# Sound_Activated_LED_Schematic.net
KiCad netlist of a schematic drawn in EAGLE
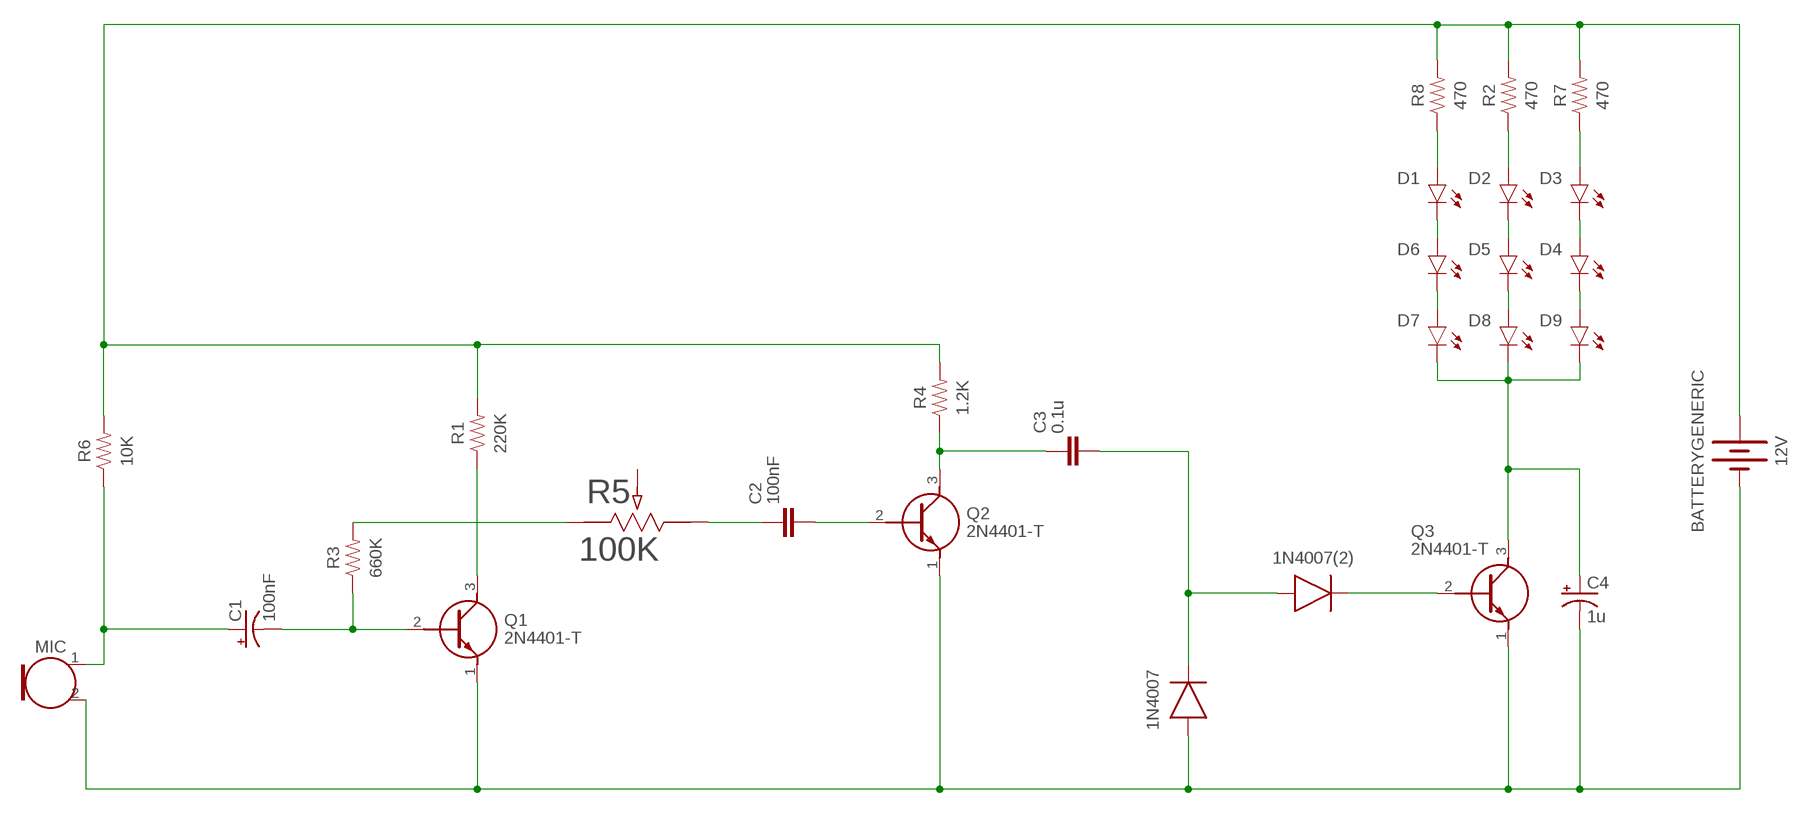
[diagram p0: schematic, sheet 1]

(export (version "E")
  (design (tool "Eeschema 10.0.6"))
  (components
    (comp (ref "1N4007")
      (value "DIODE_1N4148W-7-F_SOD123G")
      (footprint "eagle-import:SOD3715X135")
      (fields (field (name "MANUFACTURER") "Diodes Incorporated") (field (name "MPN") "1N4148W-7-F"))
      (libsource (lib "eagle-import") (part "DIODE__SOD123G1N4148W-7-F"))
    )
    (comp (ref "1N4007(2)")
      (value "DIODE_1N4148W-7-F_SOD123G")
      (footprint "eagle-import:SOD3715X135")
      (fields (field (name "MANUFACTURER") "Diodes Incorporated") (field (name "MPN") "1N4148W-7-F"))
      (libsource (lib "eagle-import") (part "DIODE__SOD123G1N4148W-7-F"))
    )
    (comp (ref "12V")
      (value "BATTERYGENERIC")
      (footprint "eagle-import:BATTERY-GENERIC")
      (libsource (lib "eagle-import") (part "BATTERYGENERIC"))
    )
    (comp (ref "C1")
      (value "100nF")
      (footprint "eagle-import:CAPMP3216X180N")
      (libsource (lib "eagle-import") (part "C-POL-USTANTALUM-1206(3216-METRIC)_"))
    )
    (comp (ref "C2")
      (value "100nF")
      (footprint "eagle-import:CAPC1005X60")
      (libsource (lib "eagle-import") (part "CCHIP-0402(1005-METRIC)_"))
    )
    (comp (ref "C3")
      (value "0.1u")
      (footprint "eagle-import:CAPC1005X60")
      (libsource (lib "eagle-import") (part "CCHIP-0402(1005-METRIC)_"))
    )
    (comp (ref "C4")
      (value "1u")
      (footprint "eagle-import:CAPMP3216X180N")
      (libsource (lib "eagle-import") (part "C-POL-USTANTALUM-1206(3216-METRIC)_"))
    )
    (comp (ref "D1")
      (value "CHIP-ROUND-R_0603")
      (footprint "eagle-import:LEDC1608X65N_RND-R")
      (libsource (lib "eagle-import") (part "CHIP-ROUND-R_0603"))
    )
    (comp (ref "D2")
      (value "CHIP-ROUND-R_0603")
      (footprint "eagle-import:LEDC1608X65N_RND-R")
      (libsource (lib "eagle-import") (part "CHIP-ROUND-R_0603"))
    )
    (comp (ref "D3")
      (value "CHIP-ROUND-R_0603")
      (footprint "eagle-import:LEDC1608X65N_RND-R")
      (libsource (lib "eagle-import") (part "CHIP-ROUND-R_0603"))
    )
    (comp (ref "D4")
      (value "CHIP-ROUND-R_0603")
      (footprint "eagle-import:LEDC1608X65N_RND-R")
      (libsource (lib "eagle-import") (part "CHIP-ROUND-R_0603"))
    )
    (comp (ref "D5")
      (value "CHIP-ROUND-R_0603")
      (footprint "eagle-import:LEDC1608X65N_RND-R")
      (libsource (lib "eagle-import") (part "CHIP-ROUND-R_0603"))
    )
    (comp (ref "D6")
      (value "CHIP-ROUND-R_0603")
      (footprint "eagle-import:LEDC1608X65N_RND-R")
      (libsource (lib "eagle-import") (part "CHIP-ROUND-R_0603"))
    )
    (comp (ref "D7")
      (value "CHIP-ROUND-R_0603")
      (footprint "eagle-import:LEDC1608X65N_RND-R")
      (libsource (lib "eagle-import") (part "CHIP-ROUND-R_0603"))
    )
    (comp (ref "D8")
      (value "CHIP-ROUND-R_0603")
      (footprint "eagle-import:LEDC1608X65N_RND-R")
      (libsource (lib "eagle-import") (part "CHIP-ROUND-R_0603"))
    )
    (comp (ref "D9")
      (value "CHIP-ROUND-R_0603")
      (footprint "eagle-import:LEDC1608X65N_RND-R")
      (libsource (lib "eagle-import") (part "CHIP-ROUND-R_0603"))
    )
    (comp (ref "MIC")
      (value "CMA-4544PF-W")
      (footprint "eagle-import:CMA-4544PF-W")
      (fields (field (name "MANUFACTURER") "Same Sky"))
      (libsource (lib "eagle-import") (part "CMA-4544PF-W"))
    )
    (comp (ref "Q1")
      (value "2N4401-T")
      (footprint "eagle-import:2N4401T")
      (fields (field (name "MOUSER_PART_NUMBER") "583-2N4401-T"))
      (libsource (lib "eagle-import") (part "2N4401-T"))
    )
    (comp (ref "Q2")
      (value "2N4401-T")
      (footprint "eagle-import:2N4401T")
      (fields (field (name "MOUSER_PART_NUMBER") "583-2N4401-T"))
      (libsource (lib "eagle-import") (part "2N4401-T"))
    )
    (comp (ref "Q3")
      (value "2N4401-T")
      (footprint "eagle-import:2N4401T")
      (fields (field (name "MOUSER_PART_NUMBER") "583-2N4401-T"))
      (libsource (lib "eagle-import") (part "2N4401-T"))
    )
    (comp (ref "R1")
      (value "220K")
      (footprint "eagle-import:RESC1005X40")
      (libsource (lib "eagle-import") (part "R-USCHIP-0402(1005-METRIC)_"))
    )
    (comp (ref "R2")
      (value "470")
      (footprint "eagle-import:RESC1005X40")
      (libsource (lib "eagle-import") (part "R-USCHIP-0402(1005-METRIC)_"))
    )
    (comp (ref "R3")
      (value "660K")
      (footprint "eagle-import:RESC1005X40")
      (libsource (lib "eagle-import") (part "R-USCHIP-0402(1005-METRIC)_"))
    )
    (comp (ref "R4")
      (value "1.2K")
      (footprint "eagle-import:RESC1005X40")
      (libsource (lib "eagle-import") (part "R-USCHIP-0402(1005-METRIC)_"))
    )
    (comp (ref "R5")
      (value "100K")
      (footprint "eagle-import:POT_1623757-2")
      (fields
        (field (name "MANUFACTURER_PART_NUMBER") "23ESA103MMF50NF")
        (field (name "COPYRIGHT") "Copyright (C) 2016 Accelerated Designs. All rights reserved")
      )
      (libsource (lib "eagle-import") (part "1623760-2"))
    )
    (comp (ref "R6")
      (value "10K")
      (footprint "eagle-import:RESC1005X40")
      (libsource (lib "eagle-import") (part "R-USCHIP-0402(1005-METRIC)_"))
    )
    (comp (ref "R7")
      (value "470")
      (footprint "eagle-import:RESC1005X40")
      (libsource (lib "eagle-import") (part "R-USCHIP-0402(1005-METRIC)_"))
    )
    (comp (ref "R8")
      (value "470")
      (footprint "eagle-import:RESC1005X40")
      (libsource (lib "eagle-import") (part "R-USCHIP-0402(1005-METRIC)_"))
    )
  )
  (nets
    (net (code "1") (name "Net-(1N4007(2)-A)") (class "Default")
      (node (ref "1N4007") (pin "1") (pinfunction "C_1") (pintype "passive"))
      (node (ref "1N4007(2)") (pin "2") (pinfunction "A_2") (pintype "passive"))
      (node (ref "C3") (pin "2") (pinfunction "2_2") (pintype "passive"))
    )
    (net (code "2") (name "Net-(1N4007(2)-C)") (class "Default")
      (node (ref "1N4007(2)") (pin "1") (pinfunction "C_1") (pintype "passive"))
      (node (ref "Q3") (pin "2") (pinfunction "B_2") (pintype "bidirectional"))
    )
    (net (code "3") (name "Net-(1N4007-A)") (class "Default")
      (node (ref "12V") (pin "-") (pinfunction "-_-") (pintype "passive"))
      (node (ref "1N4007") (pin "2") (pinfunction "A_2") (pintype "passive"))
      (node (ref "C4") (pin "2") (pinfunction "-_2") (pintype "passive"))
      (node (ref "MIC") (pin "2") (pinfunction "GND_2") (pintype "output"))
      (node (ref "Q1") (pin "1") (pinfunction "E_1") (pintype "bidirectional"))
      (node (ref "Q2") (pin "1") (pinfunction "E_1") (pintype "bidirectional"))
      (node (ref "Q3") (pin "1") (pinfunction "E_1") (pintype "bidirectional"))
    )
    (net (code "4") (name "Net-(12V-Pad+)") (class "Default")
      (node (ref "12V") (pin "+") (pinfunction "+_+") (pintype "passive"))
      (node (ref "R1") (pin "2") (pinfunction "2_2") (pintype "passive"))
      (node (ref "R2") (pin "2") (pinfunction "2_2") (pintype "passive"))
      (node (ref "R4") (pin "2") (pinfunction "2_2") (pintype "passive"))
      (node (ref "R6") (pin "2") (pinfunction "2_2") (pintype "passive"))
      (node (ref "R7") (pin "2") (pinfunction "2_2") (pintype "passive"))
      (node (ref "R8") (pin "2") (pinfunction "2_2") (pintype "passive"))
    )
    (net (code "5") (name "Net-(C1-+)") (class "Default")
      (node (ref "C1") (pin "1") (pinfunction "+_1") (pintype "passive"))
      (node (ref "MIC") (pin "1") (pinfunction "OUT_1") (pintype "power_in"))
      (node (ref "R6") (pin "1") (pinfunction "1_1") (pintype "passive"))
    )
    (net (code "6") (name "Net-(C1--)") (class "Default")
      (node (ref "C1") (pin "2") (pinfunction "-_2") (pintype "passive"))
      (node (ref "Q1") (pin "2") (pinfunction "B_2") (pintype "bidirectional"))
      (node (ref "R3") (pin "1") (pinfunction "1_1") (pintype "passive"))
    )
    (net (code "7") (name "Net-(C2-Pad1)") (class "Default")
      (node (ref "C2") (pin "1") (pinfunction "1_1") (pintype "passive"))
      (node (ref "R5") (pin "3") (pinfunction "3_3") (pintype "passive"))
    )
    (net (code "8") (name "Net-(C4-+)") (class "Default")
      (node (ref "C4") (pin "1") (pinfunction "+_1") (pintype "passive"))
      (node (ref "D7") (pin "C") (pinfunction "C_C") (pintype "passive"))
      (node (ref "D8") (pin "C") (pinfunction "C_C") (pintype "passive"))
      (node (ref "D9") (pin "C") (pinfunction "C_C") (pintype "passive"))
      (node (ref "Q3") (pin "3") (pinfunction "C_3") (pintype "bidirectional"))
    )
    (net (code "9") (name "Net-(D1-PadA)") (class "Default")
      (node (ref "D1") (pin "A") (pinfunction "A_A") (pintype "passive"))
      (node (ref "R8") (pin "1") (pinfunction "1_1") (pintype "passive"))
    )
    (net (code "10") (name "Net-(D1-PadC)") (class "Default")
      (node (ref "D1") (pin "C") (pinfunction "C_C") (pintype "passive"))
      (node (ref "D6") (pin "A") (pinfunction "A_A") (pintype "passive"))
    )
    (net (code "11") (name "Net-(D2-PadA)") (class "Default")
      (node (ref "D2") (pin "A") (pinfunction "A_A") (pintype "passive"))
      (node (ref "R2") (pin "1") (pinfunction "1_1") (pintype "passive"))
    )
    (net (code "12") (name "Net-(D2-PadC)") (class "Default")
      (node (ref "D2") (pin "C") (pinfunction "C_C") (pintype "passive"))
      (node (ref "D5") (pin "A") (pinfunction "A_A") (pintype "passive"))
    )
    (net (code "13") (name "Net-(D3-PadA)") (class "Default")
      (node (ref "D3") (pin "A") (pinfunction "A_A") (pintype "passive"))
      (node (ref "R7") (pin "1") (pinfunction "1_1") (pintype "passive"))
    )
    (net (code "14") (name "Net-(D3-PadC)") (class "Default")
      (node (ref "D3") (pin "C") (pinfunction "C_C") (pintype "passive"))
      (node (ref "D4") (pin "A") (pinfunction "A_A") (pintype "passive"))
    )
    (net (code "15") (name "Net-(D4-PadC)") (class "Default")
      (node (ref "D4") (pin "C") (pinfunction "C_C") (pintype "passive"))
      (node (ref "D9") (pin "A") (pinfunction "A_A") (pintype "passive"))
    )
    (net (code "16") (name "Net-(D5-PadC)") (class "Default")
      (node (ref "D5") (pin "C") (pinfunction "C_C") (pintype "passive"))
      (node (ref "D8") (pin "A") (pinfunction "A_A") (pintype "passive"))
    )
    (net (code "17") (name "Net-(D6-PadC)") (class "Default")
      (node (ref "D6") (pin "C") (pinfunction "C_C") (pintype "passive"))
      (node (ref "D7") (pin "A") (pinfunction "A_A") (pintype "passive"))
    )
    (net (code "18") (name "Net-(Q1-C)") (class "Default")
      (node (ref "Q1") (pin "3") (pinfunction "C_3") (pintype "bidirectional"))
      (node (ref "R1") (pin "1") (pinfunction "1_1") (pintype "passive"))
    )
    (net (code "19") (name "Net-(Q2-B)") (class "Default")
      (node (ref "C2") (pin "2") (pinfunction "2_2") (pintype "passive"))
      (node (ref "Q2") (pin "2") (pinfunction "B_2") (pintype "bidirectional"))
    )
    (net (code "20") (name "Net-(Q2-C)") (class "Default")
      (node (ref "C3") (pin "1") (pinfunction "1_1") (pintype "passive"))
      (node (ref "Q2") (pin "3") (pinfunction "C_3") (pintype "bidirectional"))
      (node (ref "R4") (pin "1") (pinfunction "1_1") (pintype "passive"))
    )
    (net (code "21") (name "Net-(R3-Pad2)") (class "Default")
      (node (ref "R3") (pin "2") (pinfunction "2_2") (pintype "passive"))
      (node (ref "R5") (pin "1") (pinfunction "1_1") (pintype "passive"))
    )
    (net (code "22") (name "unconnected-(R5-Pad2)") (class "Default")
      (node (ref "R5") (pin "2") (pinfunction "2_2") (pintype "passive"))
    )
  )
)
